# 4_Communicate.net
KiCad netlist of a schematic drawn in Altium Designer
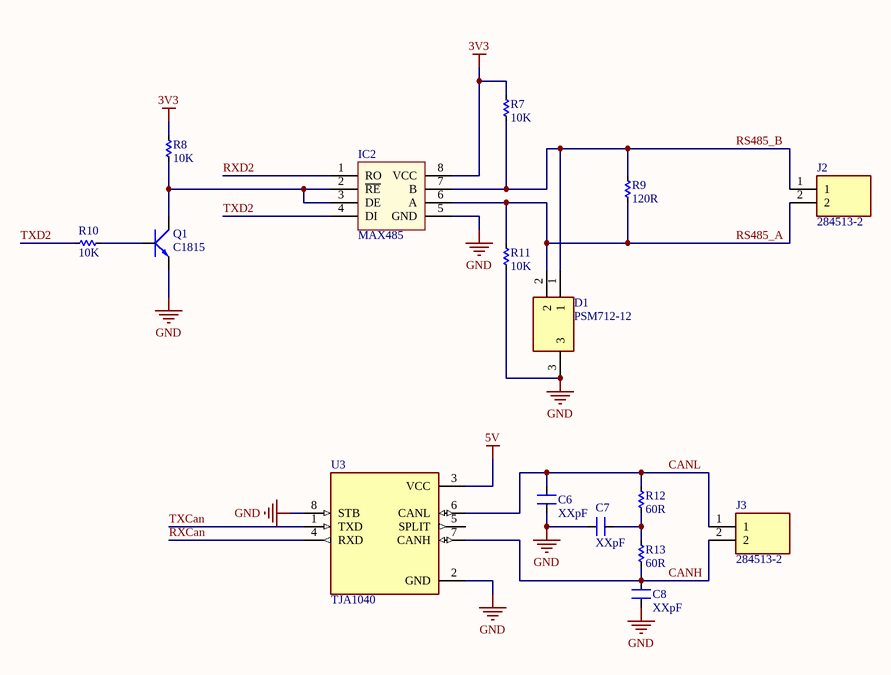
[diagram p0: [4]Communicate.SchDoc]

(export (version "E")
  (design (tool "Eeschema 10.0.6"))
  (components
    (comp (ref "C6") (value "XXpF") (footprint "CN-SMD-0805") (libsource (lib "LIBRARY") (part "CN")))
    (comp (ref "C7") (value "XXpF") (footprint "CN-SMD-0805") (libsource (lib "LIBRARY") (part "CN")))
    (comp (ref "C8") (value "XXpF") (footprint "CN-SMD-0805") (libsource (lib "LIBRARY") (part "CN")))
    (comp (ref "D1")
      (value "PSM712-12")
      (footprint "SamacSys:PSM71212")
      (description "TVS Diode (Bi-directional)")
      (libsource (lib "*") (part "PSM712-12"))
    )
    (comp (ref "IC2")
      (value "MAX485")
      (footprint "SO8")
      (description "RS232 - RS485 (Same sn75176)")
      (libsource (lib "LIBRARY") (part "MAX485"))
    )
    (comp (ref "J2")
      (value "284513-2")
      (footprint "SamacSys:SHDRRA2W80P0X381_1X2_863X920X730P")
      (description "Connector")
      (fields (field (name "MOUSER PART NUMBER") "571-284513-2"))
      (libsource (lib "SamacSys") (part "284513-2"))
    )
    (comp (ref "J3")
      (value "284513-2")
      (footprint "SamacSys:SHDRRA2W80P0X381_1X2_863X920X730P")
      (description "Connector")
      (fields (field (name "MOUSER PART NUMBER") "571-284513-2"))
      (libsource (lib "SamacSys") (part "284513-2"))
    )
    (comp (ref "Q1")
      (value "C1815")
      (footprint "SOT23B")
      (description "NPN 600mW, ECB")
      (libsource (lib "electronicvn-library1") (part "C1815"))
    )
    (comp (ref "R7")
      (value "10K")
      (footprint "RES-SMD-0805")
      (description "Resistor")
      (fields
        (field (name "MANUFACTURER") "Generic Components")
        (field (name "PUBLISHER") "Altium Hobart Technology Centre")
      )
      (libsource (lib "LIBRARY") (part "Res-SMD"))
    )
    (comp (ref "R8")
      (value "10K")
      (footprint "RES-SMD-0805")
      (description "Resistor")
      (fields
        (field (name "MANUFACTURER") "Generic Components")
        (field (name "PUBLISHER") "Altium Hobart Technology Centre")
      )
      (libsource (lib "LIBRARY") (part "Res-SMD"))
    )
    (comp (ref "R9")
      (value "120R")
      (footprint "RES-SMD-0805")
      (description "Resistor")
      (fields
        (field (name "MANUFACTURER") "Generic Components")
        (field (name "PUBLISHER") "Altium Hobart Technology Centre")
      )
      (libsource (lib "LIBRARY") (part "Res-SMD"))
    )
    (comp (ref "R10")
      (value "10K")
      (footprint "RES-SMD-0805")
      (description "Resistor")
      (fields
        (field (name "MANUFACTURER") "Generic Components")
        (field (name "PUBLISHER") "Altium Hobart Technology Centre")
      )
      (libsource (lib "LIBRARY") (part "Res-SMD"))
    )
    (comp (ref "R11")
      (value "10K")
      (footprint "RES-SMD-0805")
      (description "Resistor")
      (fields
        (field (name "MANUFACTURER") "Generic Components")
        (field (name "PUBLISHER") "Altium Hobart Technology Centre")
      )
      (libsource (lib "LIBRARY") (part "Res-SMD"))
    )
    (comp (ref "R12")
      (value "60R")
      (footprint "RES-SMD-0805")
      (description "Resistor")
      (fields
        (field (name "MANUFACTURER") "Generic Components")
        (field (name "PUBLISHER") "Altium Hobart Technology Centre")
      )
      (libsource (lib "LIBRARY") (part "Res-SMD"))
    )
    (comp (ref "R13")
      (value "60R")
      (footprint "RES-SMD-0805")
      (description "Resistor")
      (fields
        (field (name "MANUFACTURER") "Generic Components")
        (field (name "PUBLISHER") "Altium Hobart Technology Centre")
      )
      (libsource (lib "LIBRARY") (part "Res-SMD"))
    )
    (comp (ref "U3")
      (value "TJA1040")
      (footprint "SOIC127P600X175-8N")
      (description "1/1 Transceiver Half CANbus 8-SO")
      (fields (field (name "MF") "NXP USA"))
      (libsource (lib "TJA1040") (part "TJA1040"))
    )
  )
  (nets
    (net (code "1") (name "/CANH") (class "Default")
      (node (ref "C8") (pin "2") (pinfunction "2_2") (pintype "passive"))
      (node (ref "J3") (pin "2") (pinfunction "2_2") (pintype "passive"))
      (node (ref "R13") (pin "2") (pinfunction "2_2") (pintype "passive"))
      (node (ref "U3") (pin "7") (pinfunction "CANH_7") (pintype "bidirectional"))
    )
    (net (code "2") (name "/CANL") (class "Default")
      (node (ref "C6") (pin "2") (pinfunction "2_2") (pintype "passive"))
      (node (ref "J3") (pin "1") (pinfunction "1_1") (pintype "passive"))
      (node (ref "R12") (pin "1") (pinfunction "1_1") (pintype "passive"))
      (node (ref "U3") (pin "6") (pinfunction "CANL_6") (pintype "bidirectional"))
    )
    (net (code "3") (name "/RS485_A") (class "Default")
      (node (ref "D1") (pin "2") (pinfunction "2_2") (pintype "passive"))
      (node (ref "IC2") (pin "6") (pinfunction "A_6") (pintype "passive"))
      (node (ref "J2") (pin "2") (pinfunction "2_2") (pintype "passive"))
      (node (ref "R11") (pin "2") (pinfunction "2_2") (pintype "passive"))
      (node (ref "R9") (pin "1") (pinfunction "1_1") (pintype "passive"))
    )
    (net (code "4") (name "/RS485_B") (class "Default")
      (node (ref "D1") (pin "1") (pinfunction "1_1") (pintype "passive"))
      (node (ref "IC2") (pin "7") (pinfunction "B_7") (pintype "passive"))
      (node (ref "J2") (pin "1") (pinfunction "1_1") (pintype "passive"))
      (node (ref "R7") (pin "1") (pinfunction "1_1") (pintype "passive"))
      (node (ref "R9") (pin "2") (pinfunction "2_2") (pintype "passive"))
    )
    (net (code "5") (name "/RXCan") (class "Default")
      (node (ref "U3") (pin "4") (pinfunction "RXD_4") (pintype "output"))
    )
    (net (code "6") (name "/RXD2") (class "Default")
      (node (ref "IC2") (pin "1") (pinfunction "RO_1") (pintype "passive"))
    )
    (net (code "7") (name "/TXCan") (class "Default")
      (node (ref "U3") (pin "1") (pinfunction "TXD_1") (pintype "input"))
    )
    (net (code "8") (name "/TXD2") (class "Default")
      (node (ref "IC2") (pin "4") (pinfunction "DI_4") (pintype "passive"))
      (node (ref "R10") (pin "1") (pinfunction "1_1") (pintype "passive"))
    )
    (net (code "9") (name "3V3") (class "Default")
      (node (ref "IC2") (pin "8") (pinfunction "VCC_8") (pintype "passive"))
      (node (ref "R7") (pin "2") (pinfunction "2_2") (pintype "passive"))
      (node (ref "R8") (pin "2") (pinfunction "2_2") (pintype "passive"))
    )
    (net (code "10") (name "5V") (class "Default")
      (node (ref "U3") (pin "3") (pinfunction "VCC_3") (pintype "power_in"))
    )
    (net (code "11") (name "GND") (class "Default")
      (node (ref "C6") (pin "1") (pinfunction "1_1") (pintype "passive"))
      (node (ref "C7") (pin "1") (pinfunction "1_1") (pintype "passive"))
      (node (ref "C8") (pin "1") (pinfunction "1_1") (pintype "passive"))
      (node (ref "D1") (pin "3") (pinfunction "3_3") (pintype "passive"))
      (node (ref "IC2") (pin "5") (pinfunction "GND_5") (pintype "passive"))
      (node (ref "Q1") (pin "1") (pinfunction "E_1") (pintype "passive"))
      (node (ref "R11") (pin "1") (pinfunction "1_1") (pintype "passive"))
      (node (ref "U3") (pin "2") (pinfunction "GND_2") (pintype "power_in"))
      (node (ref "U3") (pin "8") (pinfunction "STB_8") (pintype "input"))
    )
    (net (code "12") (name "Net-(C7-Pad2)") (class "Default")
      (node (ref "C7") (pin "2") (pinfunction "2_2") (pintype "passive"))
      (node (ref "R12") (pin "2") (pinfunction "2_2") (pintype "passive"))
      (node (ref "R13") (pin "1") (pinfunction "1_1") (pintype "passive"))
    )
    (net (code "13") (name "Net-(IC2-DE)") (class "Default")
      (node (ref "IC2") (pin "2") (pinfunction "~{RE}_2") (pintype "passive"))
      (node (ref "IC2") (pin "3") (pinfunction "DE_3") (pintype "passive"))
      (node (ref "Q1") (pin "2") (pinfunction "C_2") (pintype "passive"))
      (node (ref "R8") (pin "1") (pinfunction "1_1") (pintype "passive"))
    )
    (net (code "14") (name "Net-(Q1-B)") (class "Default")
      (node (ref "Q1") (pin "3") (pinfunction "B_3") (pintype "passive"))
      (node (ref "R10") (pin "2") (pinfunction "2_2") (pintype "passive"))
    )
    (net (code "15") (name "unconnected-(U3-SPLIT-Pad5)") (class "Default")
      (node (ref "U3") (pin "5") (pinfunction "SPLIT_5") (pintype "output"))
    )
  )
)
